# PET_Diag_KB.net
KiCad netlist of a schematic drawn in EAGLE
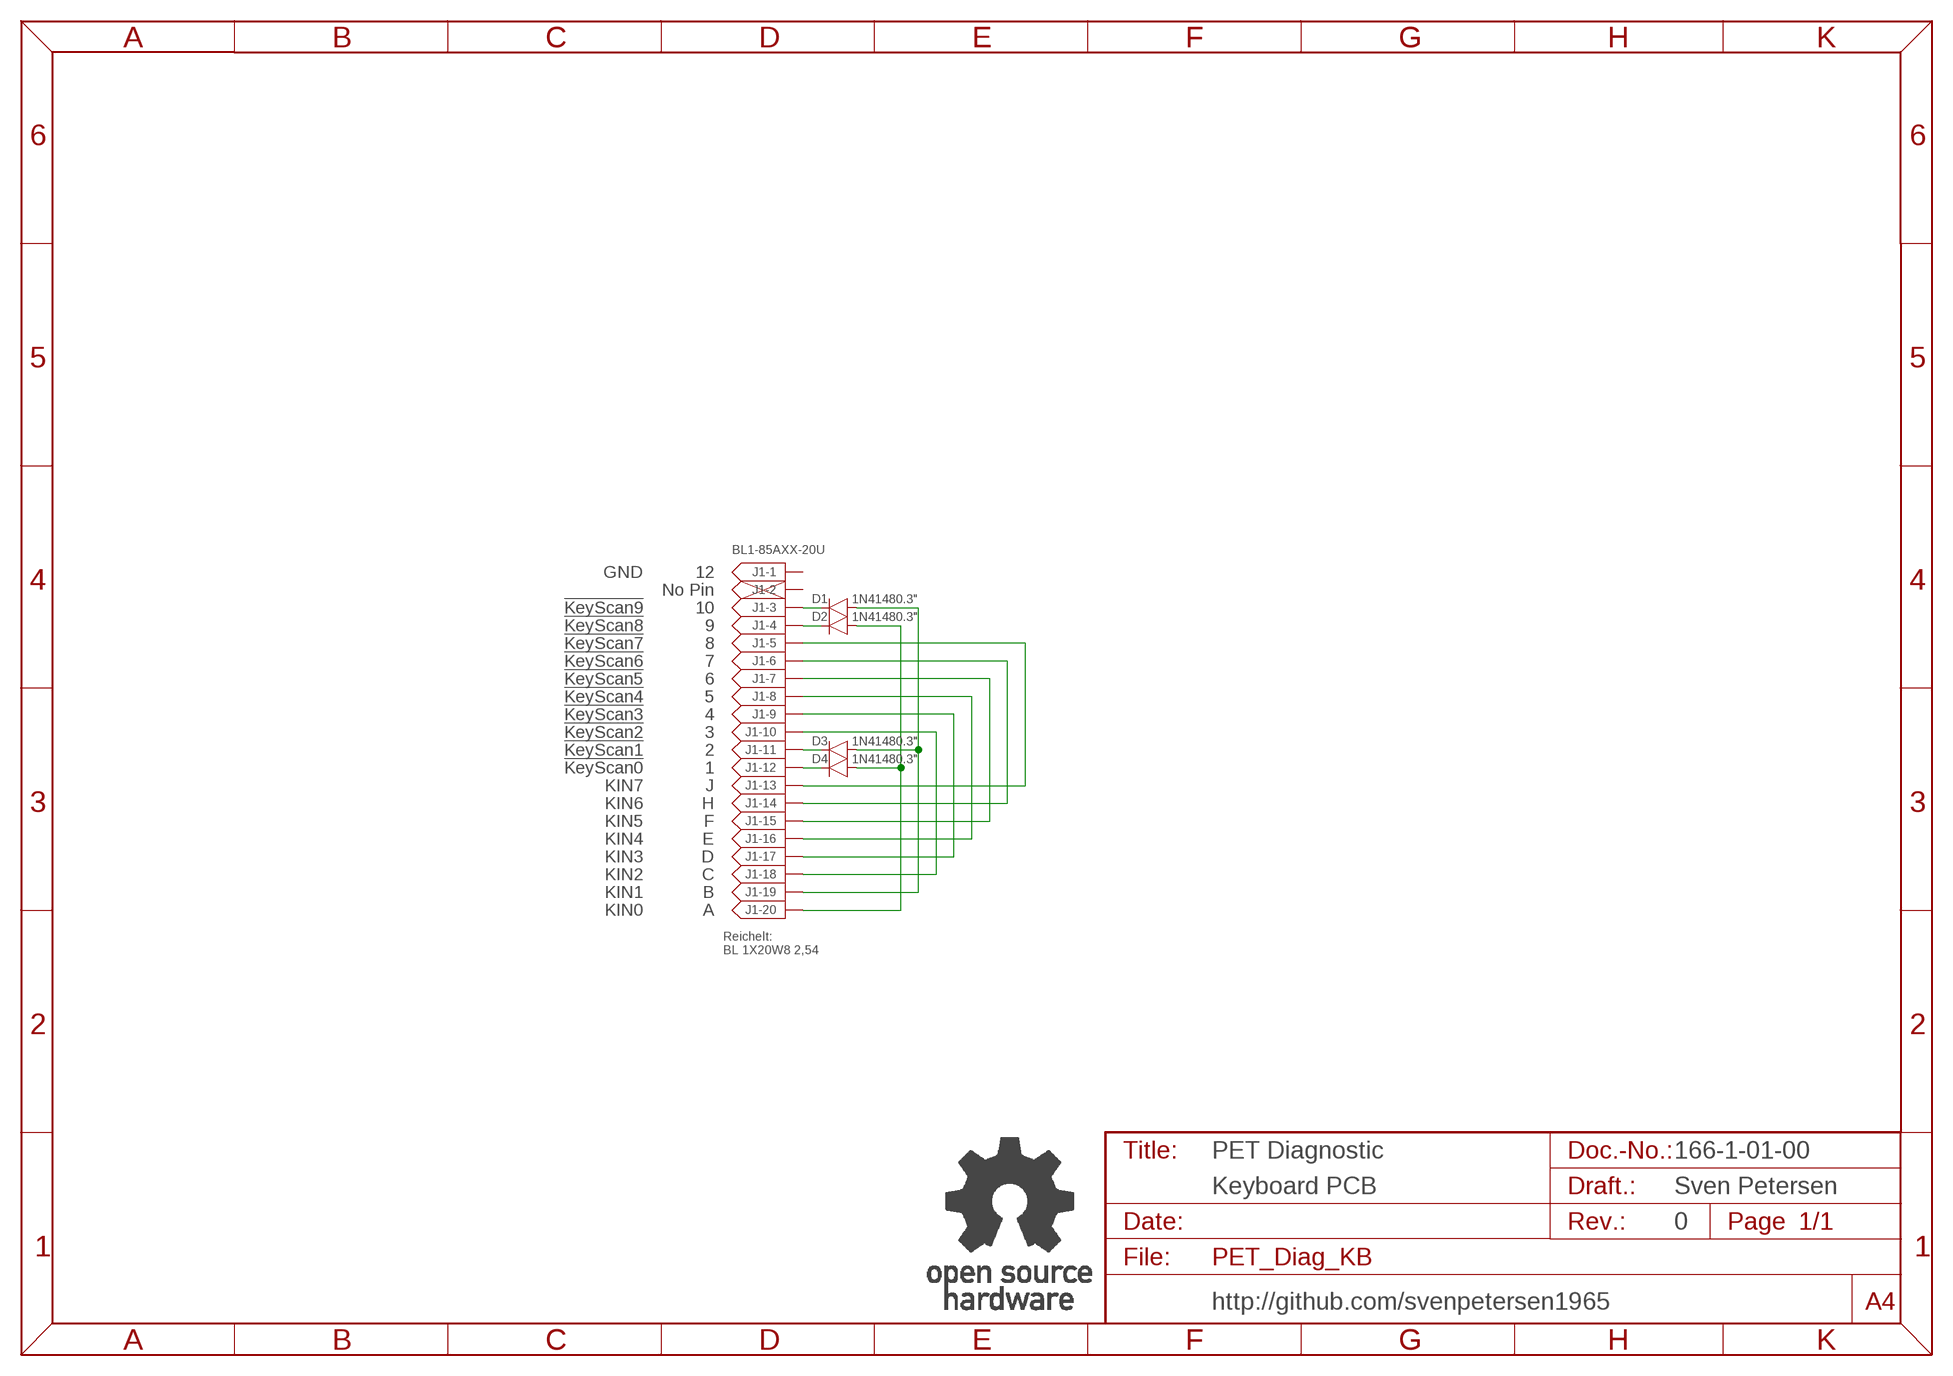
[diagram p0: schematic, sheet 1]

(export (version "E")
  (design (tool "Eeschema 10.0.6"))
  (components
    (comp (ref "D1")
      (value "1N41480.3\"")
      (footprint "eagle-import:DO-35_3")
      (libsource (lib "eagle-import") (part "1N41480.3{dblquote}"))
    )
    (comp (ref "D2")
      (value "1N41480.3\"")
      (footprint "eagle-import:DO-35_3")
      (libsource (lib "eagle-import") (part "1N41480.3{dblquote}"))
    )
    (comp (ref "D3")
      (value "1N41480.3\"")
      (footprint "eagle-import:DO-35_3")
      (libsource (lib "eagle-import") (part "1N41480.3{dblquote}"))
    )
    (comp (ref "D4")
      (value "1N41480.3\"")
      (footprint "eagle-import:DO-35_3")
      (libsource (lib "eagle-import") (part "1N41480.3{dblquote}"))
    )
    (comp (ref "J1")
      (value "BL1-85AXX-20U")
      (footprint "eagle-import:BL1-85AXX-20U")
      (libsource (lib "eagle-import") (part "BL1-85AXX-20U"))
    )
    (comp (ref "U$9")
      (value "OPEN_SOURCE_HW")
      (footprint "eagle-import:OPENHW")
      (libsource (lib "eagle-import") (part "OPEN_SOURCE_HW"))
    )
  )
  (nets
    (net (code "1") (name "Net-(J1B-1)") (class "Default")
      (node (ref "J1") (pin "10") (pinfunction "1_10") (pintype "bidirectional"))
      (node (ref "J1") (pin "18") (pinfunction "1_18") (pintype "bidirectional"))
    )
    (net (code "2") (name "Net-(J1C-1)") (class "Default")
      (node (ref "D3") (pin "K") (pinfunction "K_K") (pintype "passive"))
      (node (ref "J1") (pin "11") (pinfunction "1_11") (pintype "bidirectional"))
    )
    (net (code "3") (name "Net-(J1D-1)") (class "Default")
      (node (ref "D4") (pin "K") (pinfunction "K_K") (pintype "passive"))
      (node (ref "J1") (pin "12") (pinfunction "1_12") (pintype "bidirectional"))
    )
    (net (code "4") (name "Net-(J1E-1)") (class "Default")
      (node (ref "J1") (pin "13") (pinfunction "1_13") (pintype "bidirectional"))
      (node (ref "J1") (pin "5") (pinfunction "1_5") (pintype "bidirectional"))
    )
    (net (code "5") (name "Net-(J1F-1)") (class "Default")
      (node (ref "J1") (pin "14") (pinfunction "1_14") (pintype "bidirectional"))
      (node (ref "J1") (pin "6") (pinfunction "1_6") (pintype "bidirectional"))
    )
    (net (code "6") (name "Net-(J1G-1)") (class "Default")
      (node (ref "J1") (pin "15") (pinfunction "1_15") (pintype "bidirectional"))
      (node (ref "J1") (pin "7") (pinfunction "1_7") (pintype "bidirectional"))
    )
    (net (code "7") (name "Net-(J1H-1)") (class "Default")
      (node (ref "J1") (pin "16") (pinfunction "1_16") (pintype "bidirectional"))
      (node (ref "J1") (pin "8") (pinfunction "1_8") (pintype "bidirectional"))
    )
    (net (code "8") (name "Net-(J1I-1)") (class "Default")
      (node (ref "J1") (pin "17") (pinfunction "1_17") (pintype "bidirectional"))
      (node (ref "J1") (pin "9") (pinfunction "1_9") (pintype "bidirectional"))
    )
    (net (code "9") (name "Net-(J1K-1)") (class "Default")
      (node (ref "D1") (pin "A") (pinfunction "A_A") (pintype "passive"))
      (node (ref "D3") (pin "A") (pinfunction "A_A") (pintype "passive"))
      (node (ref "J1") (pin "19") (pinfunction "1_19") (pintype "bidirectional"))
    )
    (net (code "10") (name "Net-(J1M-1)") (class "Default")
      (node (ref "D2") (pin "A") (pinfunction "A_A") (pintype "passive"))
      (node (ref "D4") (pin "A") (pinfunction "A_A") (pintype "passive"))
      (node (ref "J1") (pin "20") (pinfunction "1_20") (pintype "bidirectional"))
    )
    (net (code "11") (name "Net-(J1N-1)") (class "Default")
      (node (ref "D1") (pin "K") (pinfunction "K_K") (pintype "passive"))
      (node (ref "J1") (pin "3") (pinfunction "1_3") (pintype "bidirectional"))
    )
    (net (code "12") (name "Net-(J1O-1)") (class "Default")
      (node (ref "D2") (pin "K") (pinfunction "K_K") (pintype "passive"))
      (node (ref "J1") (pin "4") (pinfunction "1_4") (pintype "bidirectional"))
    )
    (net (code "13") (name "unconnected-(J1-Pad1)") (class "Default")
      (node (ref "J1") (pin "1") (pinfunction "1_1") (pintype "bidirectional"))
    )
    (net (code "14") (name "unconnected-(J1L-1-Pad2)") (class "Default")
      (node (ref "J1") (pin "2") (pinfunction "1_2") (pintype "bidirectional"))
    )
  )
)
